# FedorBall.net
KiCad netlist of a schematic drawn in EAGLE
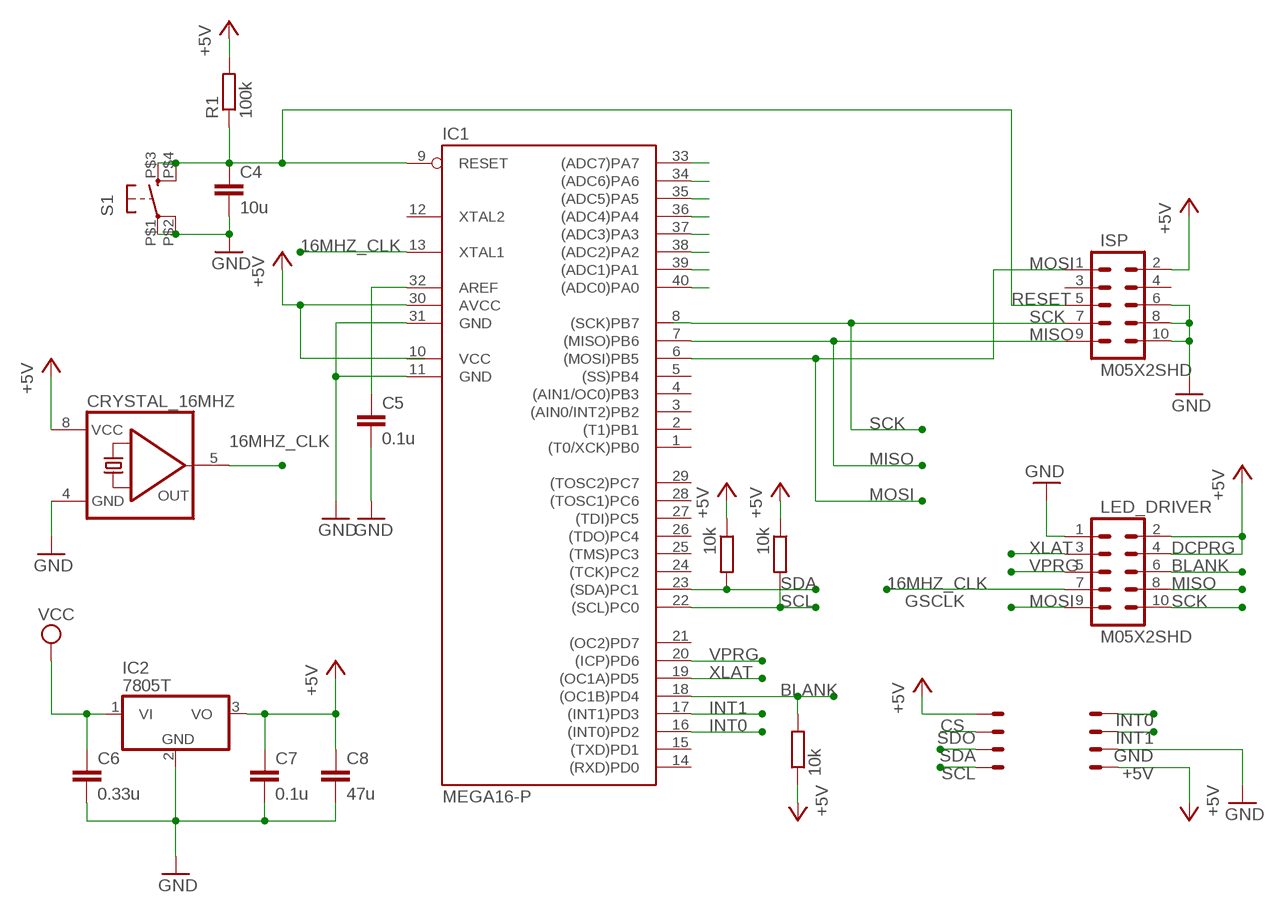
[diagram p0: schematic, sheet 1]

(export (version "E")
  (design (tool "Eeschema 10.0.6"))
  (components
    (comp (ref "C4")
      (value "10u")
      (footprint "eagle-import:C050-024X044")
      (libsource (lib "eagle-import") (part "C-EU050-024X044"))
    )
    (comp (ref "C5")
      (value "0.1u")
      (footprint "eagle-import:C050-024X044")
      (libsource (lib "eagle-import") (part "C-EU050-024X044"))
    )
    (comp (ref "C6")
      (value "0.33u")
      (footprint "eagle-import:C050-024X044")
      (libsource (lib "eagle-import") (part "C-EU050-024X044"))
    )
    (comp (ref "C7")
      (value "0.1u")
      (footprint "eagle-import:C050-024X044")
      (libsource (lib "eagle-import") (part "C-EU050-024X044"))
    )
    (comp (ref "C8")
      (value "47u")
      (footprint "eagle-import:C050-024X044")
      (libsource (lib "eagle-import") (part "C-EU050-024X044"))
    )
    (comp (ref "CRYSTAL_16MHZ")
      (value "QG5460")
      (footprint "eagle-import:DIL08S")
      (libsource (lib "eagle-import") (part "QG5460"))
    )
    (comp (ref "IC1")
      (value "MEGA16-P")
      (footprint "eagle-import:DIL40")
      (fields (field (name "MPN") "ATMEGA16-16PU"))
      (libsource (lib "eagle-import") (part "MEGA16-P"))
    )
    (comp (ref "IC2")
      (value "7805T")
      (footprint "eagle-import:TO220H")
      (libsource (lib "eagle-import") (part "78T05"))
    )
    (comp (ref "ISP")
      (value "M05X2SHD")
      (footprint "eagle-import:2X5-SHROUDED")
      (libsource (lib "eagle-import") (part "M05X2SHD"))
    )
    (comp (ref "LED_DRIVER")
      (value "M05X2SHD")
      (footprint "eagle-import:2X5-SHROUDED")
      (libsource (lib "eagle-import") (part "M05X2SHD"))
    )
    (comp (ref "R1")
      (value "100k")
      (footprint "eagle-import:0207_10")
      (libsource (lib "eagle-import") (part "R-EU_0207/10"))
    )
    (comp (ref "R2")
      (value "10k")
      (footprint "eagle-import:0207_10")
      (libsource (lib "eagle-import") (part "R-EU_0207/10"))
    )
    (comp (ref "R5")
      (value "10k")
      (footprint "eagle-import:0207_10")
      (libsource (lib "eagle-import") (part "R-EU_0207/10"))
    )
    (comp (ref "R6")
      (value "10k")
      (footprint "eagle-import:0207_10")
      (libsource (lib "eagle-import") (part "R-EU_0207/10"))
    )
    (comp (ref "S1")
      (value "TAC_SWITCHKSA_SEALED")
      (footprint "eagle-import:KSA_SEALED_TAC_SWITCH")
      (libsource (lib "eagle-import") (part "TAC_SWITCHKSA_SEALED"))
    )
    (comp (ref "X1")
      (value "22-23-2041")
      (footprint "eagle-import:22-23-2041")
      (fields (field (name "MF") "MOLEX"))
      (libsource (lib "eagle-import") (part "22-23-2041"))
    )
    (comp (ref "X2")
      (value "22-23-2041")
      (footprint "eagle-import:22-23-2041")
      (fields (field (name "MF") "MOLEX"))
      (libsource (lib "eagle-import") (part "22-23-2041"))
    )
  )
  (nets
    (net (code "1") (name "+5V") (class "Default")
      (node (ref "C7") (pin "1") (pinfunction "1_1") (pintype "passive"))
      (node (ref "C8") (pin "1") (pinfunction "1_1") (pintype "passive"))
      (node (ref "CRYSTAL_16MHZ") (pin "8") (pinfunction "VCC_8") (pintype "power_in"))
      (node (ref "IC1") (pin "10") (pinfunction "VCC_10") (pintype "power_in"))
      (node (ref "IC1") (pin "30") (pinfunction "AVCC_30") (pintype "power_in"))
      (node (ref "IC2") (pin "3") (pinfunction "VO_3") (pintype "passive"))
      (node (ref "ISP") (pin "2") (pinfunction "2_2") (pintype "passive"))
      (node (ref "LED_DRIVER") (pin "2") (pinfunction "2_2") (pintype "passive"))
      (node (ref "LED_DRIVER") (pin "4") (pinfunction "4_4") (pintype "passive"))
      (node (ref "R1") (pin "2") (pinfunction "2_2") (pintype "passive"))
      (node (ref "R2") (pin "1") (pinfunction "1_1") (pintype "passive"))
      (node (ref "R5") (pin "1") (pinfunction "1_1") (pintype "passive"))
      (node (ref "R6") (pin "1") (pinfunction "1_1") (pintype "passive"))
      (node (ref "X1") (pin "1") (pinfunction "S_1") (pintype "passive"))
      (node (ref "X2") (pin "4") (pinfunction "S_4") (pintype "passive"))
    )
    (net (code "2") (name "/16MHZ_CLK") (class "Default")
      (node (ref "CRYSTAL_16MHZ") (pin "5") (pinfunction "OUT_5") (pintype "output"))
      (node (ref "IC1") (pin "13") (pinfunction "XTAL1_13") (pintype "bidirectional"))
      (node (ref "LED_DRIVER") (pin "7") (pinfunction "7_7") (pintype "passive"))
    )
    (net (code "3") (name "/BLANK") (class "Default")
      (node (ref "IC1") (pin "18") (pinfunction "(OC1B)PD4_18") (pintype "bidirectional"))
      (node (ref "LED_DRIVER") (pin "6") (pinfunction "6_6") (pintype "passive"))
      (node (ref "R2") (pin "2") (pinfunction "2_2") (pintype "passive"))
    )
    (net (code "4") (name "/INT0") (class "Default")
      (node (ref "IC1") (pin "16") (pinfunction "(INT0)PD2_16") (pintype "bidirectional"))
      (node (ref "X1") (pin "4") (pinfunction "S_4") (pintype "passive"))
    )
    (net (code "5") (name "/INT1") (class "Default")
      (node (ref "IC1") (pin "17") (pinfunction "(INT1)PD3_17") (pintype "bidirectional"))
      (node (ref "X1") (pin "3") (pinfunction "S_3") (pintype "passive"))
    )
    (net (code "6") (name "/MISO") (class "Default")
      (node (ref "IC1") (pin "7") (pinfunction "(MISO)PB6_7") (pintype "bidirectional"))
      (node (ref "ISP") (pin "9") (pinfunction "9_9") (pintype "passive"))
      (node (ref "LED_DRIVER") (pin "8") (pinfunction "8_8") (pintype "passive"))
    )
    (net (code "7") (name "/MOSI") (class "Default")
      (node (ref "IC1") (pin "6") (pinfunction "(MOSI)PB5_6") (pintype "bidirectional"))
      (node (ref "ISP") (pin "1") (pinfunction "1_1") (pintype "passive"))
      (node (ref "LED_DRIVER") (pin "9") (pinfunction "9_9") (pintype "passive"))
    )
    (net (code "8") (name "/SCK") (class "Default")
      (node (ref "IC1") (pin "8") (pinfunction "(SCK)PB7_8") (pintype "bidirectional"))
      (node (ref "ISP") (pin "7") (pinfunction "7_7") (pintype "passive"))
      (node (ref "LED_DRIVER") (pin "10") (pinfunction "10_10") (pintype "passive"))
    )
    (net (code "9") (name "/SCL") (class "Default")
      (node (ref "IC1") (pin "22") (pinfunction "(SCL)PC0_22") (pintype "bidirectional"))
      (node (ref "R6") (pin "2") (pinfunction "2_2") (pintype "passive"))
      (node (ref "X2") (pin "1") (pinfunction "S_1") (pintype "passive"))
    )
    (net (code "10") (name "/SDA") (class "Default")
      (node (ref "IC1") (pin "23") (pinfunction "(SDA)PC1_23") (pintype "bidirectional"))
      (node (ref "R5") (pin "2") (pinfunction "2_2") (pintype "passive"))
      (node (ref "X2") (pin "2") (pinfunction "S_2") (pintype "passive"))
    )
    (net (code "11") (name "/SDO") (class "Default")
      (node (ref "X2") (pin "3") (pinfunction "S_3") (pintype "passive"))
    )
    (net (code "12") (name "/VPRG") (class "Default")
      (node (ref "IC1") (pin "20") (pinfunction "(ICP)PD6_20") (pintype "bidirectional"))
      (node (ref "LED_DRIVER") (pin "5") (pinfunction "5_5") (pintype "passive"))
    )
    (net (code "13") (name "/XLAT") (class "Default")
      (node (ref "IC1") (pin "19") (pinfunction "(OC1A)PD5_19") (pintype "bidirectional"))
      (node (ref "LED_DRIVER") (pin "3") (pinfunction "3_3") (pintype "passive"))
    )
    (net (code "14") (name "GND") (class "Default")
      (node (ref "C4") (pin "2") (pinfunction "2_2") (pintype "passive"))
      (node (ref "C5") (pin "2") (pinfunction "2_2") (pintype "passive"))
      (node (ref "C6") (pin "2") (pinfunction "2_2") (pintype "passive"))
      (node (ref "C7") (pin "2") (pinfunction "2_2") (pintype "passive"))
      (node (ref "C8") (pin "2") (pinfunction "2_2") (pintype "passive"))
      (node (ref "CRYSTAL_16MHZ") (pin "4") (pinfunction "GND_4") (pintype "power_in"))
      (node (ref "IC1") (pin "11") (pinfunction "GND_11") (pintype "power_in"))
      (node (ref "IC1") (pin "31") (pinfunction "GND_31") (pintype "power_in"))
      (node (ref "IC2") (pin "2") (pinfunction "GND_2") (pintype "passive"))
      (node (ref "ISP") (pin "10") (pinfunction "10_10") (pintype "passive"))
      (node (ref "ISP") (pin "6") (pinfunction "6_6") (pintype "passive"))
      (node (ref "ISP") (pin "8") (pinfunction "8_8") (pintype "passive"))
      (node (ref "LED_DRIVER") (pin "1") (pinfunction "1_1") (pintype "passive"))
      (node (ref "S1") (pin "P$1") (pinfunction "1_P$1") (pintype "passive"))
      (node (ref "S1") (pin "P$2") (pinfunction "2_P$2") (pintype "passive"))
      (node (ref "X1") (pin "2") (pinfunction "S_2") (pintype "passive"))
    )
    (net (code "15") (name "Net-(IC1-AREF)") (class "Default")
      (node (ref "C5") (pin "1") (pinfunction "1_1") (pintype "passive"))
      (node (ref "IC1") (pin "32") (pinfunction "AREF_32") (pintype "passive"))
    )
    (net (code "16") (name "Net-(IC1-RESET)") (class "Default")
      (node (ref "C4") (pin "1") (pinfunction "1_1") (pintype "passive"))
      (node (ref "IC1") (pin "9") (pinfunction "RESET_9") (pintype "input"))
      (node (ref "ISP") (pin "5") (pinfunction "5_5") (pintype "passive"))
      (node (ref "R1") (pin "1") (pinfunction "1_1") (pintype "passive"))
      (node (ref "S1") (pin "P$3") (pinfunction "3_P$3") (pintype "passive"))
      (node (ref "S1") (pin "P$4") (pinfunction "4_P$4") (pintype "passive"))
    )
    (net (code "17") (name "VCC") (class "Default")
      (node (ref "C6") (pin "1") (pinfunction "1_1") (pintype "passive"))
      (node (ref "IC2") (pin "1") (pinfunction "VI_1") (pintype "input"))
    )
    (net (code "18") (name "unconnected-(IC1-(ADC0)PA0-Pad40)") (class "Default")
      (node (ref "IC1") (pin "40") (pinfunction "(ADC0)PA0_40") (pintype "bidirectional"))
    )
    (net (code "19") (name "unconnected-(IC1-(ADC1)PA1-Pad39)") (class "Default")
      (node (ref "IC1") (pin "39") (pinfunction "(ADC1)PA1_39") (pintype "bidirectional"))
    )
    (net (code "20") (name "unconnected-(IC1-(ADC2)PA2-Pad38)") (class "Default")
      (node (ref "IC1") (pin "38") (pinfunction "(ADC2)PA2_38") (pintype "bidirectional"))
    )
    (net (code "21") (name "unconnected-(IC1-(ADC3)PA3-Pad37)") (class "Default")
      (node (ref "IC1") (pin "37") (pinfunction "(ADC3)PA3_37") (pintype "bidirectional"))
    )
    (net (code "22") (name "unconnected-(IC1-(ADC4)PA4-Pad36)") (class "Default")
      (node (ref "IC1") (pin "36") (pinfunction "(ADC4)PA4_36") (pintype "bidirectional"))
    )
    (net (code "23") (name "unconnected-(IC1-(ADC5)PA5-Pad35)") (class "Default")
      (node (ref "IC1") (pin "35") (pinfunction "(ADC5)PA5_35") (pintype "bidirectional"))
    )
    (net (code "24") (name "unconnected-(IC1-(ADC6)PA6-Pad34)") (class "Default")
      (node (ref "IC1") (pin "34") (pinfunction "(ADC6)PA6_34") (pintype "bidirectional"))
    )
    (net (code "25") (name "unconnected-(IC1-(ADC7)PA7-Pad33)") (class "Default")
      (node (ref "IC1") (pin "33") (pinfunction "(ADC7)PA7_33") (pintype "bidirectional"))
    )
    (net (code "26") (name "unconnected-(IC1-(AIN0{slash}INT2)PB2-Pad3)") (class "Default")
      (node (ref "IC1") (pin "3") (pinfunction "(AIN0/INT2)PB2_3") (pintype "bidirectional"))
    )
    (net (code "27") (name "unconnected-(IC1-(AIN1{slash}OC0)PB3-Pad4)") (class "Default")
      (node (ref "IC1") (pin "4") (pinfunction "(AIN1/OC0)PB3_4") (pintype "bidirectional"))
    )
    (net (code "28") (name "unconnected-(IC1-(OC2)PD7-Pad21)") (class "Default")
      (node (ref "IC1") (pin "21") (pinfunction "(OC2)PD7_21") (pintype "bidirectional"))
    )
    (net (code "29") (name "unconnected-(IC1-(RXD)PD0-Pad14)") (class "Default")
      (node (ref "IC1") (pin "14") (pinfunction "(RXD)PD0_14") (pintype "bidirectional"))
    )
    (net (code "30") (name "unconnected-(IC1-(SS)PB4-Pad5)") (class "Default")
      (node (ref "IC1") (pin "5") (pinfunction "(SS)PB4_5") (pintype "bidirectional"))
    )
    (net (code "31") (name "unconnected-(IC1-(T0{slash}XCK)PB0-Pad1)") (class "Default")
      (node (ref "IC1") (pin "1") (pinfunction "(T0/XCK)PB0_1") (pintype "bidirectional"))
    )
    (net (code "32") (name "unconnected-(IC1-(T1)PB1-Pad2)") (class "Default")
      (node (ref "IC1") (pin "2") (pinfunction "(T1)PB1_2") (pintype "bidirectional"))
    )
    (net (code "33") (name "unconnected-(IC1-(TCK)PC2-Pad24)") (class "Default")
      (node (ref "IC1") (pin "24") (pinfunction "(TCK)PC2_24") (pintype "bidirectional"))
    )
    (net (code "34") (name "unconnected-(IC1-(TDI)PC5-Pad27)") (class "Default")
      (node (ref "IC1") (pin "27") (pinfunction "(TDI)PC5_27") (pintype "bidirectional"))
    )
    (net (code "35") (name "unconnected-(IC1-(TDO)PC4-Pad26)") (class "Default")
      (node (ref "IC1") (pin "26") (pinfunction "(TDO)PC4_26") (pintype "bidirectional"))
    )
    (net (code "36") (name "unconnected-(IC1-(TMS)PC3-Pad25)") (class "Default")
      (node (ref "IC1") (pin "25") (pinfunction "(TMS)PC3_25") (pintype "bidirectional"))
    )
    (net (code "37") (name "unconnected-(IC1-(TOSC1)PC6-Pad28)") (class "Default")
      (node (ref "IC1") (pin "28") (pinfunction "(TOSC1)PC6_28") (pintype "bidirectional"))
    )
    (net (code "38") (name "unconnected-(IC1-(TOSC2)PC7-Pad29)") (class "Default")
      (node (ref "IC1") (pin "29") (pinfunction "(TOSC2)PC7_29") (pintype "bidirectional"))
    )
    (net (code "39") (name "unconnected-(IC1-(TXD)PD1-Pad15)") (class "Default")
      (node (ref "IC1") (pin "15") (pinfunction "(TXD)PD1_15") (pintype "bidirectional"))
    )
    (net (code "40") (name "unconnected-(IC1-XTAL2-Pad12)") (class "Default")
      (node (ref "IC1") (pin "12") (pinfunction "XTAL2_12") (pintype "bidirectional"))
    )
    (net (code "41") (name "unconnected-(ISP-Pad3)") (class "Default")
      (node (ref "ISP") (pin "3") (pinfunction "3_3") (pintype "passive"))
    )
    (net (code "42") (name "unconnected-(ISP-Pad4)") (class "Default")
      (node (ref "ISP") (pin "4") (pinfunction "4_4") (pintype "passive"))
    )
  )
)
